# macro_keyboard_sch.net
KiCad netlist of a schematic drawn in EAGLE
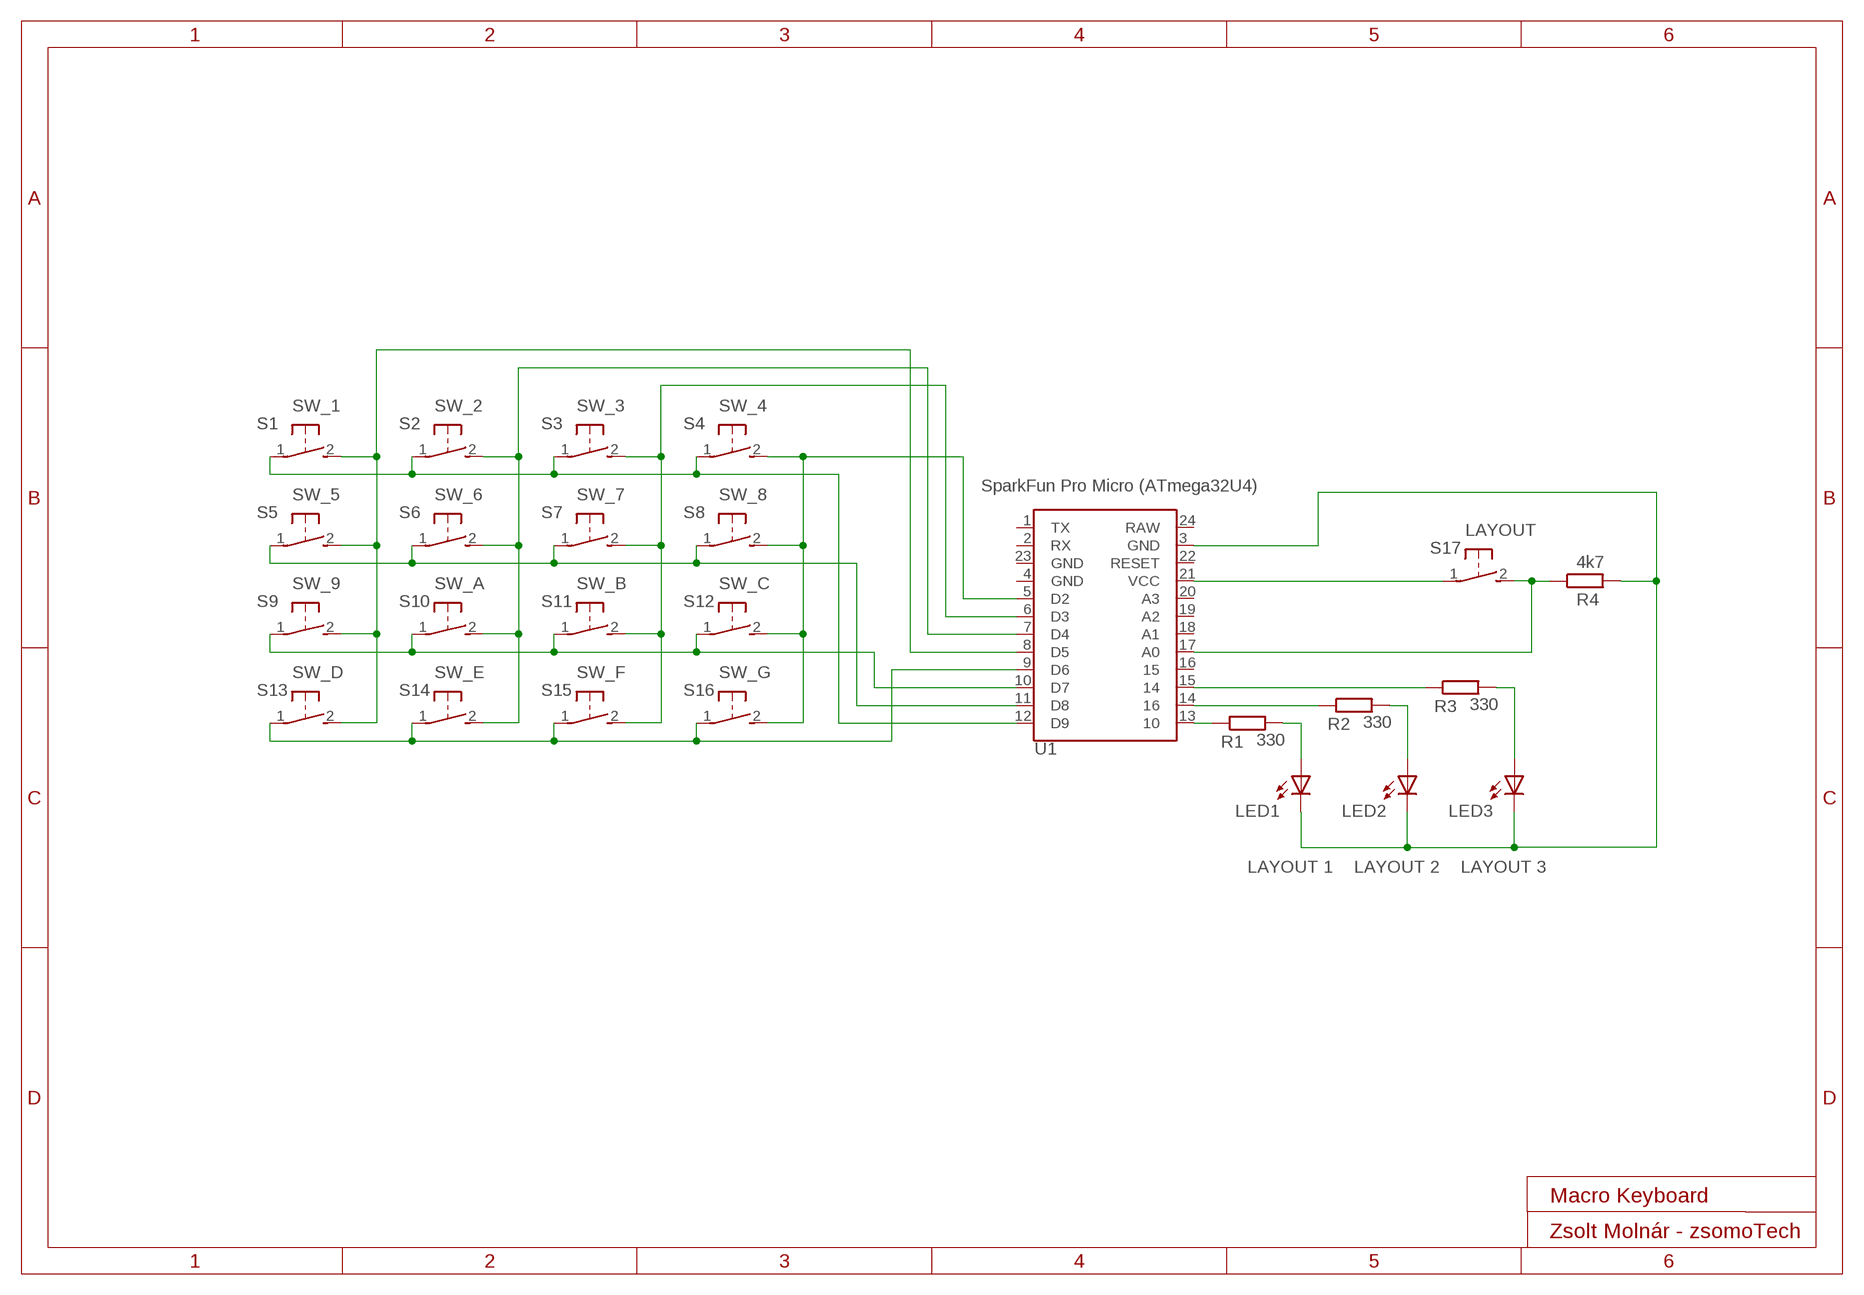
[diagram p0: schematic, sheet 1]

(export (version "E")
  (design (tool "Eeschema 10.0.6"))
  (components
    (comp (ref "LED1")
      (value "LAYOUT 1")
      (footprint "eagle-import:LED5MM")
      (libsource (lib "eagle-import") (part "LED5MM"))
    )
    (comp (ref "LED2")
      (value "LAYOUT 2")
      (footprint "eagle-import:LED5MM")
      (libsource (lib "eagle-import") (part "LED5MM"))
    )
    (comp (ref "LED3")
      (value "LAYOUT 3")
      (footprint "eagle-import:LED5MM")
      (libsource (lib "eagle-import") (part "LED5MM"))
    )
    (comp (ref "R1")
      (value "330")
      (footprint "eagle-import:0207_10")
      (libsource (lib "eagle-import") (part "R0207/10"))
    )
    (comp (ref "R2")
      (value "330")
      (footprint "eagle-import:0207_10")
      (libsource (lib "eagle-import") (part "R0207/10"))
    )
    (comp (ref "R3")
      (value "330")
      (footprint "eagle-import:0207_10")
      (libsource (lib "eagle-import") (part "R0207/10"))
    )
    (comp (ref "R4")
      (value "4k7")
      (footprint "eagle-import:0207_10")
      (libsource (lib "eagle-import") (part "R0207/10"))
    )
    (comp (ref "S1")
      (value "SW_1")
      (footprint "eagle-import:DTS-3")
      (libsource (lib "eagle-import") (part "DTS-3"))
    )
    (comp (ref "S2")
      (value "SW_2")
      (footprint "eagle-import:DTS-3")
      (libsource (lib "eagle-import") (part "DTS-3"))
    )
    (comp (ref "S3")
      (value "SW_3")
      (footprint "eagle-import:DTS-3")
      (libsource (lib "eagle-import") (part "DTS-3"))
    )
    (comp (ref "S4")
      (value "SW_4")
      (footprint "eagle-import:DTS-3")
      (libsource (lib "eagle-import") (part "DTS-3"))
    )
    (comp (ref "S5")
      (value "SW_5")
      (footprint "eagle-import:DTS-3")
      (libsource (lib "eagle-import") (part "DTS-3"))
    )
    (comp (ref "S6")
      (value "SW_6")
      (footprint "eagle-import:DTS-3")
      (libsource (lib "eagle-import") (part "DTS-3"))
    )
    (comp (ref "S7")
      (value "SW_7")
      (footprint "eagle-import:DTS-3")
      (libsource (lib "eagle-import") (part "DTS-3"))
    )
    (comp (ref "S8")
      (value "SW_8")
      (footprint "eagle-import:DTS-3")
      (libsource (lib "eagle-import") (part "DTS-3"))
    )
    (comp (ref "S9")
      (value "SW_9")
      (footprint "eagle-import:DTS-3")
      (libsource (lib "eagle-import") (part "DTS-3"))
    )
    (comp (ref "S10")
      (value "SW_A")
      (footprint "eagle-import:DTS-3")
      (libsource (lib "eagle-import") (part "DTS-3"))
    )
    (comp (ref "S11")
      (value "SW_B")
      (footprint "eagle-import:DTS-3")
      (libsource (lib "eagle-import") (part "DTS-3"))
    )
    (comp (ref "S12")
      (value "SW_C")
      (footprint "eagle-import:DTS-3")
      (libsource (lib "eagle-import") (part "DTS-3"))
    )
    (comp (ref "S13")
      (value "SW_D")
      (footprint "eagle-import:DTS-3")
      (libsource (lib "eagle-import") (part "DTS-3"))
    )
    (comp (ref "S14")
      (value "SW_E")
      (footprint "eagle-import:DTS-3")
      (libsource (lib "eagle-import") (part "DTS-3"))
    )
    (comp (ref "S15")
      (value "SW_F")
      (footprint "eagle-import:DTS-3")
      (libsource (lib "eagle-import") (part "DTS-3"))
    )
    (comp (ref "S16")
      (value "SW_G")
      (footprint "eagle-import:DTS-3")
      (libsource (lib "eagle-import") (part "DTS-3"))
    )
    (comp (ref "S17")
      (value "LAYOUT")
      (footprint "eagle-import:DTS-3")
      (libsource (lib "eagle-import") (part "DTS-3"))
    )
    (comp (ref "U1")
      (value "SparkFun Pro Micro (ATmega32U4)")
      (footprint "eagle-import:PRO_MICRO_C")
      (libsource (lib "eagle-import") (part "PRO_MICRO_C"))
    )
  )
  (nets
    (net (code "1") (name "Net-(LED1-C)") (class "Default")
      (node (ref "LED1") (pin "K") (pinfunction "C_K") (pintype "passive"))
      (node (ref "LED2") (pin "K") (pinfunction "C_K") (pintype "passive"))
      (node (ref "LED3") (pin "K") (pinfunction "C_K") (pintype "passive"))
      (node (ref "R4") (pin "2") (pinfunction "2_2") (pintype "passive"))
      (node (ref "U1") (pin "3") (pinfunction "GND_3") (pintype "bidirectional"))
    )
    (net (code "2") (name "Net-(LED1-PadA)") (class "Default")
      (node (ref "LED1") (pin "A") (pinfunction "A_A") (pintype "passive"))
      (node (ref "R1") (pin "2") (pinfunction "2_2") (pintype "passive"))
    )
    (net (code "3") (name "Net-(LED2-PadA)") (class "Default")
      (node (ref "LED2") (pin "A") (pinfunction "A_A") (pintype "passive"))
      (node (ref "R2") (pin "2") (pinfunction "2_2") (pintype "passive"))
    )
    (net (code "4") (name "Net-(LED3-PadA)") (class "Default")
      (node (ref "LED3") (pin "A") (pinfunction "A_A") (pintype "passive"))
      (node (ref "R3") (pin "2") (pinfunction "2_2") (pintype "passive"))
    )
    (net (code "5") (name "Net-(U1-10)") (class "Default")
      (node (ref "R1") (pin "1") (pinfunction "1_1") (pintype "passive"))
      (node (ref "U1") (pin "13") (pinfunction "10_13") (pintype "bidirectional"))
    )
    (net (code "6") (name "Net-(U1-14)") (class "Default")
      (node (ref "R3") (pin "1") (pinfunction "1_1") (pintype "passive"))
      (node (ref "U1") (pin "15") (pinfunction "14_15") (pintype "bidirectional"))
    )
    (net (code "7") (name "Net-(U1-16)") (class "Default")
      (node (ref "R2") (pin "1") (pinfunction "1_1") (pintype "passive"))
      (node (ref "U1") (pin "14") (pinfunction "16_14") (pintype "bidirectional"))
    )
    (net (code "8") (name "Net-(U1-A0)") (class "Default")
      (node (ref "R4") (pin "1") (pinfunction "1_1") (pintype "passive"))
      (node (ref "S17") (pin "2") (pinfunction "2_2") (pintype "passive"))
      (node (ref "U1") (pin "17") (pinfunction "A0_17") (pintype "bidirectional"))
    )
    (net (code "9") (name "Net-(U1-D2)") (class "Default")
      (node (ref "S12") (pin "2") (pinfunction "2_2") (pintype "passive"))
      (node (ref "S16") (pin "2") (pinfunction "2_2") (pintype "passive"))
      (node (ref "S4") (pin "2") (pinfunction "2_2") (pintype "passive"))
      (node (ref "S8") (pin "2") (pinfunction "2_2") (pintype "passive"))
      (node (ref "U1") (pin "5") (pinfunction "D2_5") (pintype "bidirectional"))
    )
    (net (code "10") (name "Net-(U1-D3)") (class "Default")
      (node (ref "S11") (pin "2") (pinfunction "2_2") (pintype "passive"))
      (node (ref "S15") (pin "2") (pinfunction "2_2") (pintype "passive"))
      (node (ref "S3") (pin "2") (pinfunction "2_2") (pintype "passive"))
      (node (ref "S7") (pin "2") (pinfunction "2_2") (pintype "passive"))
      (node (ref "U1") (pin "6") (pinfunction "D3_6") (pintype "bidirectional"))
    )
    (net (code "11") (name "Net-(U1-D4)") (class "Default")
      (node (ref "S10") (pin "2") (pinfunction "2_2") (pintype "passive"))
      (node (ref "S14") (pin "2") (pinfunction "2_2") (pintype "passive"))
      (node (ref "S2") (pin "2") (pinfunction "2_2") (pintype "passive"))
      (node (ref "S6") (pin "2") (pinfunction "2_2") (pintype "passive"))
      (node (ref "U1") (pin "7") (pinfunction "D4_7") (pintype "bidirectional"))
    )
    (net (code "12") (name "Net-(U1-D5)") (class "Default")
      (node (ref "S1") (pin "2") (pinfunction "2_2") (pintype "passive"))
      (node (ref "S13") (pin "2") (pinfunction "2_2") (pintype "passive"))
      (node (ref "S5") (pin "2") (pinfunction "2_2") (pintype "passive"))
      (node (ref "S9") (pin "2") (pinfunction "2_2") (pintype "passive"))
      (node (ref "U1") (pin "8") (pinfunction "D5_8") (pintype "bidirectional"))
    )
    (net (code "13") (name "Net-(U1-D6)") (class "Default")
      (node (ref "S13") (pin "1") (pinfunction "1_1") (pintype "passive"))
      (node (ref "S14") (pin "1") (pinfunction "1_1") (pintype "passive"))
      (node (ref "S15") (pin "1") (pinfunction "1_1") (pintype "passive"))
      (node (ref "S16") (pin "1") (pinfunction "1_1") (pintype "passive"))
      (node (ref "U1") (pin "9") (pinfunction "D6_9") (pintype "bidirectional"))
    )
    (net (code "14") (name "Net-(U1-D7)") (class "Default")
      (node (ref "S10") (pin "1") (pinfunction "1_1") (pintype "passive"))
      (node (ref "S11") (pin "1") (pinfunction "1_1") (pintype "passive"))
      (node (ref "S12") (pin "1") (pinfunction "1_1") (pintype "passive"))
      (node (ref "S9") (pin "1") (pinfunction "1_1") (pintype "passive"))
      (node (ref "U1") (pin "10") (pinfunction "D7_10") (pintype "bidirectional"))
    )
    (net (code "15") (name "Net-(U1-D8)") (class "Default")
      (node (ref "S5") (pin "1") (pinfunction "1_1") (pintype "passive"))
      (node (ref "S6") (pin "1") (pinfunction "1_1") (pintype "passive"))
      (node (ref "S7") (pin "1") (pinfunction "1_1") (pintype "passive"))
      (node (ref "S8") (pin "1") (pinfunction "1_1") (pintype "passive"))
      (node (ref "U1") (pin "11") (pinfunction "D8_11") (pintype "bidirectional"))
    )
    (net (code "16") (name "Net-(U1-D9)") (class "Default")
      (node (ref "S1") (pin "1") (pinfunction "1_1") (pintype "passive"))
      (node (ref "S2") (pin "1") (pinfunction "1_1") (pintype "passive"))
      (node (ref "S3") (pin "1") (pinfunction "1_1") (pintype "passive"))
      (node (ref "S4") (pin "1") (pinfunction "1_1") (pintype "passive"))
      (node (ref "U1") (pin "12") (pinfunction "D9_12") (pintype "bidirectional"))
    )
    (net (code "17") (name "Net-(U1-VCC)") (class "Default")
      (node (ref "S17") (pin "1") (pinfunction "1_1") (pintype "passive"))
      (node (ref "U1") (pin "21") (pinfunction "VCC_21") (pintype "bidirectional"))
    )
    (net (code "18") (name "unconnected-(U1-15-Pad16)") (class "Default")
      (node (ref "U1") (pin "16") (pinfunction "15_16") (pintype "bidirectional"))
    )
    (net (code "19") (name "unconnected-(U1-A1-Pad18)") (class "Default")
      (node (ref "U1") (pin "18") (pinfunction "A1_18") (pintype "bidirectional"))
    )
    (net (code "20") (name "unconnected-(U1-A2-Pad19)") (class "Default")
      (node (ref "U1") (pin "19") (pinfunction "A2_19") (pintype "bidirectional"))
    )
    (net (code "21") (name "unconnected-(U1-A3-Pad20)") (class "Default")
      (node (ref "U1") (pin "20") (pinfunction "A3_20") (pintype "bidirectional"))
    )
    (net (code "22") (name "unconnected-(U1-GND-Pad4)") (class "Default")
      (node (ref "U1") (pin "4") (pinfunction "GND_4") (pintype "bidirectional"))
    )
    (net (code "23") (name "unconnected-(U1-GND-Pad23)") (class "Default")
      (node (ref "U1") (pin "23") (pinfunction "GND_23") (pintype "bidirectional"))
    )
    (net (code "24") (name "unconnected-(U1-RAW-Pad24)") (class "Default")
      (node (ref "U1") (pin "24") (pinfunction "RAW_24") (pintype "bidirectional"))
    )
    (net (code "25") (name "unconnected-(U1-RESET-Pad22)") (class "Default")
      (node (ref "U1") (pin "22") (pinfunction "RESET_22") (pintype "bidirectional"))
    )
    (net (code "26") (name "unconnected-(U1-RX-Pad2)") (class "Default")
      (node (ref "U1") (pin "2") (pinfunction "RX_2") (pintype "bidirectional"))
    )
    (net (code "27") (name "unconnected-(U1-TX-Pad1)") (class "Default")
      (node (ref "U1") (pin "1") (pinfunction "TX_1") (pintype "bidirectional"))
    )
  )
)
